# Schematic.net
KiCad netlist of a schematic drawn in EAGLE
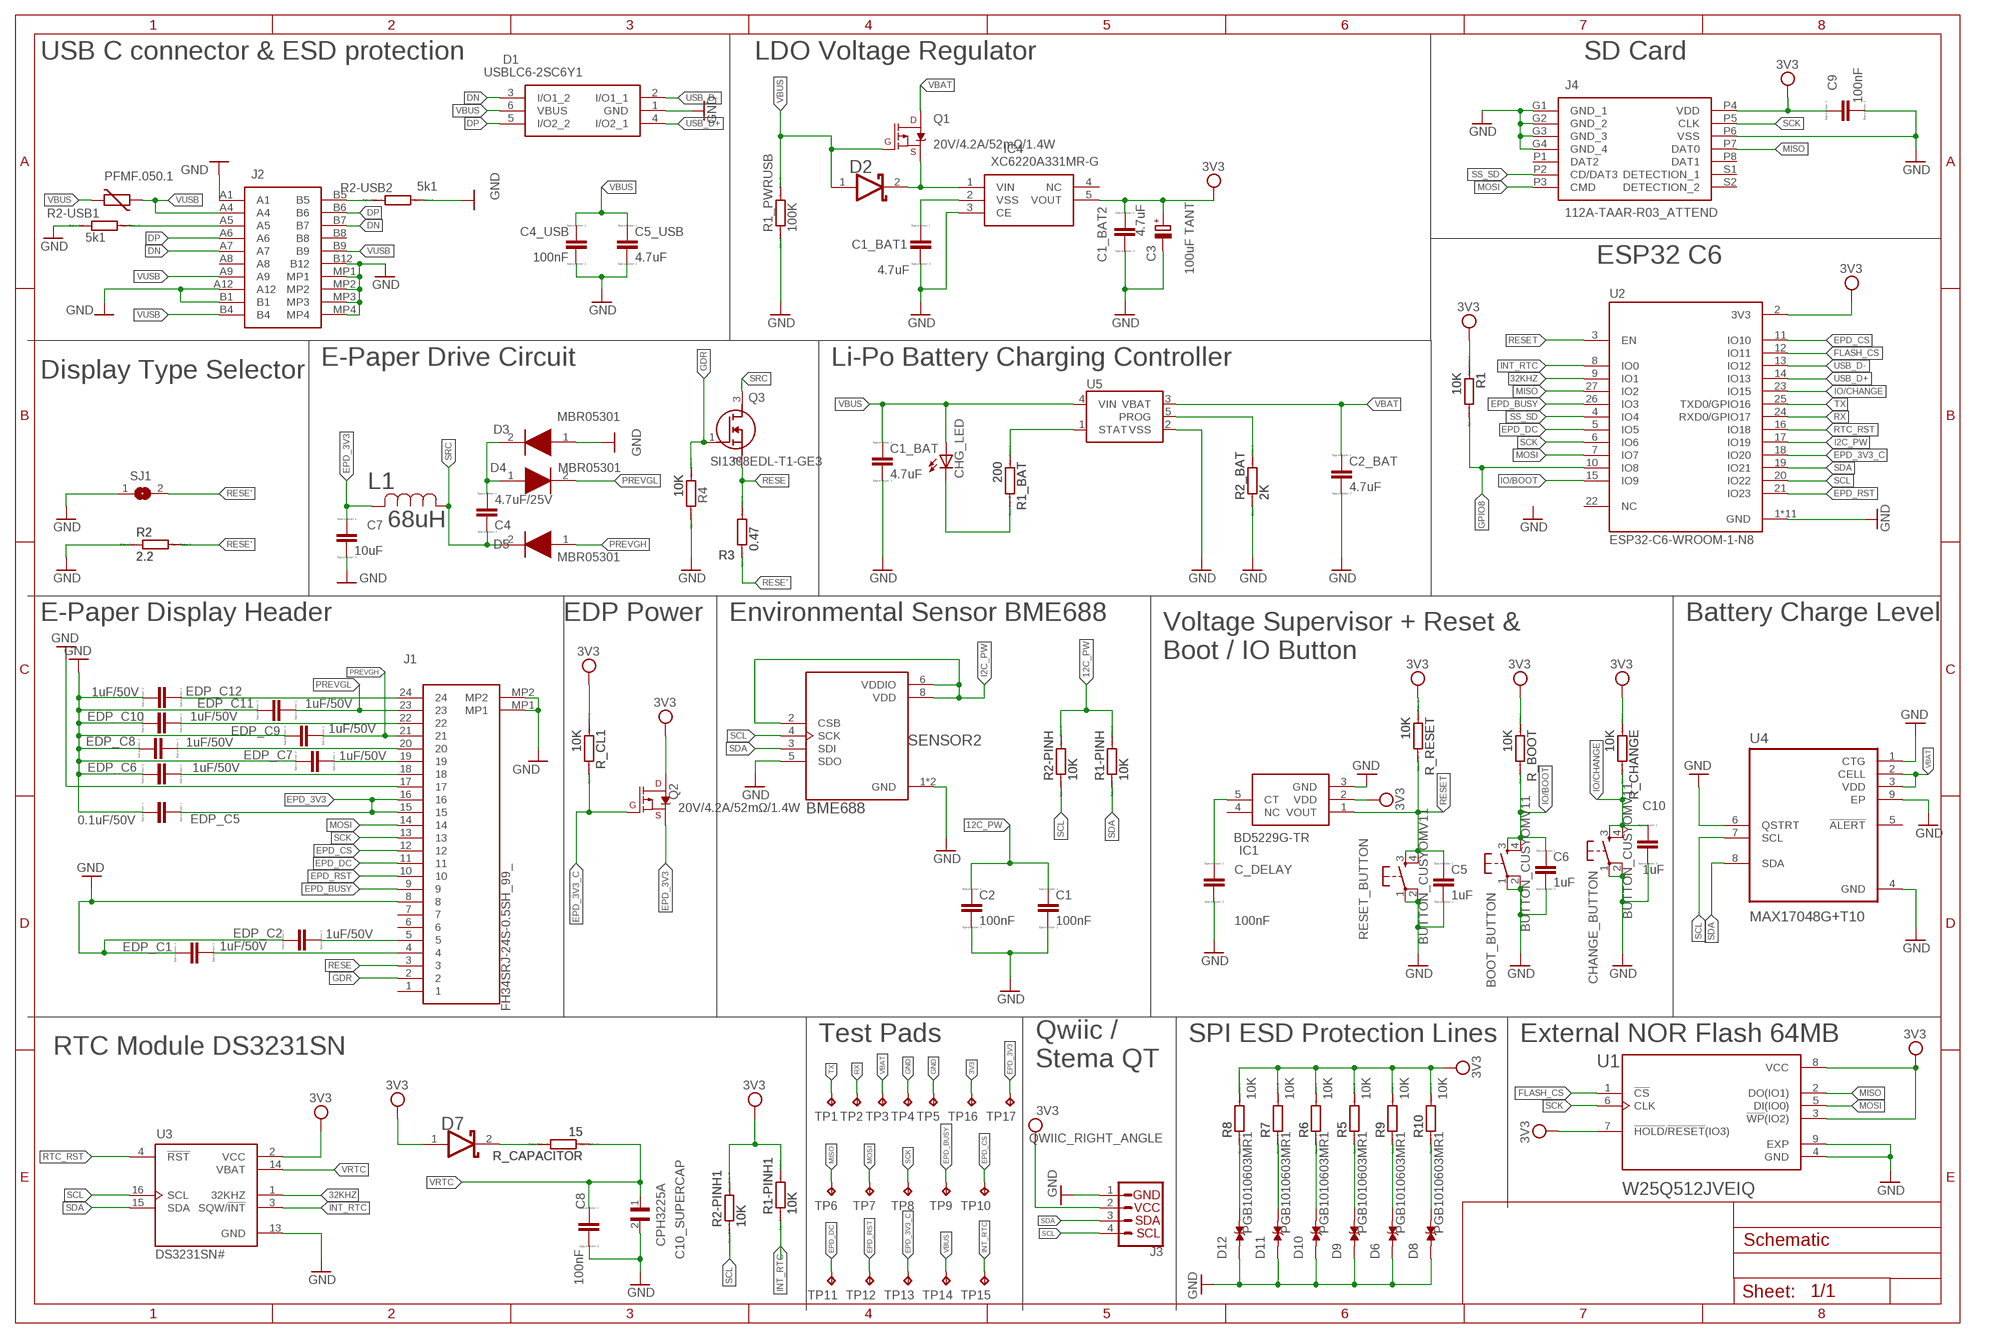
[diagram p0: schematic, sheet 1]

(export (version "E")
  (design (tool "Eeschema 10.0.6"))
  (components
    (comp (ref "BOOT_BUTTON")
      (value "BUTTON_CUSYOMV11")
      (footprint "eagle-import:MYBUTTON")
      (libsource (lib "eagle-import") (part "BUTTON_CUSYOMV11"))
    )
    (comp (ref "C1")
      (value "100nF")
      (footprint "eagle-import:ESP32_WROVER_EAGLE-LTSPICE_C0402")
      (libsource (lib "eagle-import") (part "ESP32_WROVER_EAGLE-LTSPICE_C"))
    )
    (comp (ref "C1_BAT")
      (value "4.7uF")
      (footprint "eagle-import:ESP32_WROVER_EAGLE-LTSPICE_C0402")
      (libsource (lib "eagle-import") (part "ESP32_WROVER_EAGLE-LTSPICE_C"))
    )
    (comp (ref "C1_BAT1")
      (value "4.7uF")
      (footprint "eagle-import:ESP32_WROVER_EAGLE-LTSPICE_C0402")
      (libsource (lib "eagle-import") (part "ESP32_WROVER_EAGLE-LTSPICE_C"))
    )
    (comp (ref "C1_BAT2")
      (value "4.7uF")
      (footprint "eagle-import:ESP32_WROVER_EAGLE-LTSPICE_C0402")
      (libsource (lib "eagle-import") (part "ESP32_WROVER_EAGLE-LTSPICE_C"))
    )
    (comp (ref "C2")
      (value "100nF")
      (footprint "eagle-import:ESP32_WROVER_EAGLE-LTSPICE_C0402")
      (libsource (lib "eagle-import") (part "ESP32_WROVER_EAGLE-LTSPICE_C"))
    )
    (comp (ref "C2_BAT")
      (value "4.7uF")
      (footprint "eagle-import:ESP32_WROVER_EAGLE-LTSPICE_C0402")
      (libsource (lib "eagle-import") (part "ESP32_WROVER_EAGLE-LTSPICE_C"))
    )
    (comp (ref "C3")
      (value "100uF TANT")
      (footprint "eagle-import:RCL_CT3528")
      (libsource (lib "eagle-import") (part "RCL_CPOL-EUCT3528"))
    )
    (comp (ref "C4")
      (value "4.7uF/25V")
      (footprint "eagle-import:ESP32_WROVER_EAGLE-LTSPICE_C0402")
      (libsource (lib "eagle-import") (part "ESP32_WROVER_EAGLE-LTSPICE_C"))
    )
    (comp (ref "C4_USB")
      (value "100nF")
      (footprint "eagle-import:ESP32_WROVER_EAGLE-LTSPICE_C0402")
      (libsource (lib "eagle-import") (part "ESP32_WROVER_EAGLE-LTSPICE_C"))
    )
    (comp (ref "C5")
      (value "1uF")
      (footprint "eagle-import:ESP32_WROVER_EAGLE-LTSPICE_C0402")
      (libsource (lib "eagle-import") (part "ESP32_WROVER_EAGLE-LTSPICE_C"))
    )
    (comp (ref "C5_USB")
      (value "4.7uF")
      (footprint "eagle-import:ESP32_WROVER_EAGLE-LTSPICE_C0402")
      (libsource (lib "eagle-import") (part "ESP32_WROVER_EAGLE-LTSPICE_C"))
    )
    (comp (ref "C6")
      (value "1uF")
      (footprint "eagle-import:ESP32_WROVER_EAGLE-LTSPICE_C0402")
      (libsource (lib "eagle-import") (part "ESP32_WROVER_EAGLE-LTSPICE_C"))
    )
    (comp (ref "C7")
      (value "10uF")
      (footprint "eagle-import:ESP32_WROVER_EAGLE-LTSPICE_C0402")
      (libsource (lib "eagle-import") (part "ESP32_WROVER_EAGLE-LTSPICE_C"))
    )
    (comp (ref "C8")
      (value "100nF")
      (footprint "eagle-import:ESP32_WROVER_EAGLE-LTSPICE_C0402")
      (libsource (lib "eagle-import") (part "ESP32_WROVER_EAGLE-LTSPICE_C"))
    )
    (comp (ref "C9")
      (value "100nF")
      (footprint "eagle-import:ESP32_WROVER_EAGLE-LTSPICE_C0402")
      (libsource (lib "eagle-import") (part "ESP32_WROVER_EAGLE-LTSPICE_C"))
    )
    (comp (ref "C10")
      (value "1uF")
      (footprint "eagle-import:ESP32_WROVER_EAGLE-LTSPICE_C0402")
      (libsource (lib "eagle-import") (part "ESP32_WROVER_EAGLE-LTSPICE_C"))
    )
    (comp (ref "C10_SUPERCAP")
      (value "CPH3225A")
      (footprint "eagle-import:CAPCP3225X100N")
      (fields (field (name "MF") "Seiko Instruments"))
      (libsource (lib "eagle-import") (part "CPH3225A"))
    )
    (comp (ref "CHANGE_BUTTON")
      (value "BUTTON_CUSYOMV11")
      (footprint "eagle-import:MYBUTTON")
      (libsource (lib "eagle-import") (part "BUTTON_CUSYOMV11"))
    )
    (comp (ref "CHG_LED")
      (value "1")
      (footprint "eagle-import:ADAFRUIT_CHIP-LED0603")
      (libsource (lib "eagle-import") (part "ADAFRUIT_LEDCHIP-LED0603"))
    )
    (comp (ref "C_DELAY")
      (value "100nF")
      (footprint "eagle-import:ESP32_WROVER_EAGLE-LTSPICE_C0402")
      (libsource (lib "eagle-import") (part "ESP32_WROVER_EAGLE-LTSPICE_C"))
    )
    (comp (ref "D1")
      (value "USBLC6-2SC6Y1")
      (footprint "eagle-import:SOT95P280X145-6N")
      (libsource (lib "eagle-import") (part "USBLC6-2SC6Y1"))
    )
    (comp (ref "D2")
      (value "ESP32_WROVER_AVX---SD0805S020S1R0_AVX_SD0805S020S1R0_0_0")
      (footprint "eagle-import:ESP32_WROVER_AVX---SD0805S020S1R0_AVX_SD0805S020S1R0_0")
      (libsource (lib "eagle-import") (part "ESP32_WROVER_AVX---SD0805S020S1R0_AVX_SD0805S020S1R0_0_0"))
    )
    (comp (ref "D3")
      (value "MBR05301")
      (footprint "eagle-import:SOD3716X135N")
      (libsource (lib "eagle-import") (part "MBR05301"))
    )
    (comp (ref "D4")
      (value "MBR05301")
      (footprint "eagle-import:SOD3716X135N")
      (libsource (lib "eagle-import") (part "MBR05301"))
    )
    (comp (ref "D5")
      (value "MBR05301")
      (footprint "eagle-import:SOD3716X135N")
      (libsource (lib "eagle-import") (part "MBR05301"))
    )
    (comp (ref "D6")
      (value "PGB1010603MR1")
      (footprint "eagle-import:DIOC1608X36N")
      (libsource (lib "eagle-import") (part "PGB1010603MR1"))
    )
    (comp (ref "D7")
      (value "SD805S020S1R0")
      (footprint "eagle-import:ESP32_WROVER_AVX---SD0805S020S1R0_AVX_SD0805S020S1R0_0")
      (libsource (lib "eagle-import") (part "ESP32_WROVER_AVX---SD0805S020S1R0_AVX_SD0805S020S1R0_0_0"))
    )
    (comp (ref "D8")
      (value "PGB1010603MR1")
      (footprint "eagle-import:DIOC1608X36N")
      (libsource (lib "eagle-import") (part "PGB1010603MR1"))
    )
    (comp (ref "D9")
      (value "PGB1010603MR1")
      (footprint "eagle-import:DIOC1608X36N")
      (libsource (lib "eagle-import") (part "PGB1010603MR1"))
    )
    (comp (ref "D10")
      (value "PGB1010603MR1")
      (footprint "eagle-import:DIOC1608X36N")
      (libsource (lib "eagle-import") (part "PGB1010603MR1"))
    )
    (comp (ref "D11")
      (value "PGB1010603MR1")
      (footprint "eagle-import:DIOC1608X36N")
      (libsource (lib "eagle-import") (part "PGB1010603MR1"))
    )
    (comp (ref "D12")
      (value "PGB1010603MR1")
      (footprint "eagle-import:DIOC1608X36N")
      (libsource (lib "eagle-import") (part "PGB1010603MR1"))
    )
    (comp (ref "EDP_C1")
      (value "1uF/50V")
      (footprint "eagle-import:ESP32_WROVER_EAGLE-LTSPICE_C0402")
      (libsource (lib "eagle-import") (part "ESP32_WROVER_EAGLE-LTSPICE_C"))
    )
    (comp (ref "EDP_C2")
      (value "1uF/50V")
      (footprint "eagle-import:ESP32_WROVER_EAGLE-LTSPICE_C0402")
      (libsource (lib "eagle-import") (part "ESP32_WROVER_EAGLE-LTSPICE_C"))
    )
    (comp (ref "EDP_C5")
      (value "0.1uF/50V")
      (footprint "eagle-import:ESP32_WROVER_EAGLE-LTSPICE_C0402")
      (libsource (lib "eagle-import") (part "ESP32_WROVER_EAGLE-LTSPICE_C"))
    )
    (comp (ref "EDP_C6")
      (value "1uF/50V")
      (footprint "eagle-import:ESP32_WROVER_EAGLE-LTSPICE_C0402")
      (libsource (lib "eagle-import") (part "ESP32_WROVER_EAGLE-LTSPICE_C"))
    )
    (comp (ref "EDP_C7")
      (value "1uF/50V")
      (footprint "eagle-import:ESP32_WROVER_EAGLE-LTSPICE_C0402")
      (libsource (lib "eagle-import") (part "ESP32_WROVER_EAGLE-LTSPICE_C"))
    )
    (comp (ref "EDP_C8")
      (value "1uF/50V")
      (footprint "eagle-import:ESP32_WROVER_EAGLE-LTSPICE_C0402")
      (libsource (lib "eagle-import") (part "ESP32_WROVER_EAGLE-LTSPICE_C"))
    )
    (comp (ref "EDP_C9")
      (value "1uF/50V")
      (footprint "eagle-import:ESP32_WROVER_EAGLE-LTSPICE_C0402")
      (libsource (lib "eagle-import") (part "ESP32_WROVER_EAGLE-LTSPICE_C"))
    )
    (comp (ref "EDP_C10")
      (value "1uF/50V")
      (footprint "eagle-import:ESP32_WROVER_EAGLE-LTSPICE_C0402")
      (libsource (lib "eagle-import") (part "ESP32_WROVER_EAGLE-LTSPICE_C"))
    )
    (comp (ref "EDP_C11")
      (value "1uF/50V")
      (footprint "eagle-import:ESP32_WROVER_EAGLE-LTSPICE_C0402")
      (libsource (lib "eagle-import") (part "ESP32_WROVER_EAGLE-LTSPICE_C"))
    )
    (comp (ref "EDP_C12")
      (value "1uF/50V")
      (footprint "eagle-import:ESP32_WROVER_EAGLE-LTSPICE_C0402")
      (libsource (lib "eagle-import") (part "ESP32_WROVER_EAGLE-LTSPICE_C"))
    )
    (comp (ref "IC1")
      (value "BD5229G-TR")
      (footprint "eagle-import:SOT95P280X125-5N")
      (fields (field (name "MOUSER_PART_NUMBER") "755-BD5229G-TR"))
      (libsource (lib "eagle-import") (part "BD5229G-TR"))
    )
    (comp (ref "IC4")
      (value "XC6220A331MR-G")
      (footprint "eagle-import:SOT95P280X120-5N")
      (fields (field (name "MOUSER_PART_NUMBER") "865-XC6220A331MR-G"))
      (libsource (lib "eagle-import") (part "XC6220A331MR-G"))
    )
    (comp (ref "J1")
      (value "FH34SRJ-24S-0.5SH_99_")
      (footprint "eagle-import:FH34SRJ24S05SH99")
      (fields
        (field (name "MANUFACTURER_PART_NUMBER") "FH34SRJ-24S-0.5SH(99)")
        (field (name "MOUSER_PART_NUMBER") "798-FH34SRJ24S05SH99")
      )
      (libsource (lib "eagle-import") (part "FH34SRJ-24S-0.5SH_99_"))
    )
    (comp (ref "J2")
      (value "SAMACSYS_PARTS_USB4110-GF-A")
      (footprint "eagle-import:SAMACSYS_PARTS_USB4110GFA")
      (fields
        (field (name "MANUFACTURER_PART_NUMBER") "USB4110-GF-A")
        (field (name "MOUSER_PART_NUMBER") "640-USB4110-GF-A")
      )
      (libsource (lib "eagle-import") (part "SAMACSYS_PARTS_USB4110-GF-A"))
    )
    (comp (ref "J3")
      (value "QWIIC_RIGHT_ANGLE")
      (footprint "eagle-import:JST04_1MM_RA")
      (libsource (lib "eagle-import") (part "QWIIC_CONNECTORJS-1MM"))
    )
    (comp (ref "J4")
      (value "112A-TAAR-R03_ATTEND")
      (footprint "eagle-import:112ATAARR03ATTEND")
      (fields (field (name "MANUFACTURER_PART_NUMBER") "112A-TAAR-R03 ATTEND"))
      (libsource (lib "eagle-import") (part "112A-TAAR-R03_ATTEND"))
    )
    (comp (ref "L1")
      (value "68uH")
      (footprint "eagle-import:IND_4828-WE-TPC_WRE")
      (fields
        (field (name "MANUFACTURER_PART_NUMBER") "744043680")
        (field (name "COPYRIGHT") "Copyright (C) 2024 Ultra Librarian. All rights reserved.")
      )
      (libsource (lib "eagle-import") (part "744043680IND_4828-WE-TPC_WRE"))
    )
    (comp (ref "PFMF.050.1")
      (value "ESP32C6_VARISTORCN1812")
      (footprint "eagle-import:ESP32C6_VARISTOR_CT_CN1812")
      (libsource (lib "eagle-import") (part "ESP32C6_VARISTORCN1812"))
    )
    (comp (ref "Q1")
      (value "20V/4.2A/52mΩ/1.4W")
      (footprint "eagle-import:ESP32_WROVER_SPARKFUN-DISCRETESEMI_SOT23-3")
      (libsource (lib "eagle-import") (part "ESP32_WROVER_SPARKFUN-DISCRETESEMI_MOSFET_PCH"))
    )
    (comp (ref "Q2")
      (value "20V/4.2A/52mΩ/1.4W")
      (footprint "eagle-import:ESP32_WROVER_SPARKFUN-DISCRETESEMI_SOT23-3")
      (libsource (lib "eagle-import") (part "ESP32_WROVER_SPARKFUN-DISCRETESEMI_MOSFET_PCH"))
    )
    (comp (ref "Q3")
      (value "SI1308EDL-T1-GE3")
      (footprint "eagle-import:SOT65P210X110-3N")
      (fields (field (name "MF") "Vishay Siliconix"))
      (libsource (lib "eagle-import") (part "SI1308EDL-T1-GE3"))
    )
    (comp (ref "R1")
      (value "10K")
      (footprint "eagle-import:ESP32_WROVER_EAGLE-LTSPICE_R0402")
      (libsource (lib "eagle-import") (part "ESP32_WROVER_EAGLE-LTSPICE_R"))
    )
    (comp (ref "R1-PINH")
      (value "10K")
      (footprint "eagle-import:ESP32_WROVER_EAGLE-LTSPICE_R0402")
      (libsource (lib "eagle-import") (part "ESP32_WROVER_EAGLE-LTSPICE_R"))
    )
    (comp (ref "R1-PINH1")
      (value "10K")
      (footprint "eagle-import:ESP32_WROVER_EAGLE-LTSPICE_R0402")
      (libsource (lib "eagle-import") (part "ESP32_WROVER_EAGLE-LTSPICE_R"))
    )
    (comp (ref "R1_BAT")
      (value "200")
      (footprint "eagle-import:ESP32_WROVER_EAGLE-LTSPICE_R0402")
      (libsource (lib "eagle-import") (part "ESP32_WROVER_EAGLE-LTSPICE_R"))
    )
    (comp (ref "R1_PWRUSB")
      (value "100K")
      (footprint "eagle-import:ESP32_WROVER_EAGLE-LTSPICE_R0402")
      (libsource (lib "eagle-import") (part "ESP32_WROVER_EAGLE-LTSPICE_R"))
    )
    (comp (ref "R2")
      (value "2.2")
      (footprint "eagle-import:ESP32_WROVER_EAGLE-LTSPICE_R0402")
      (libsource (lib "eagle-import") (part "ESP32_WROVER_EAGLE-LTSPICE_R"))
    )
    (comp (ref "R2-PINH")
      (value "10K")
      (footprint "eagle-import:ESP32_WROVER_EAGLE-LTSPICE_R0402")
      (libsource (lib "eagle-import") (part "ESP32_WROVER_EAGLE-LTSPICE_R"))
    )
    (comp (ref "R2-PINH1")
      (value "10K")
      (footprint "eagle-import:ESP32_WROVER_EAGLE-LTSPICE_R0402")
      (libsource (lib "eagle-import") (part "ESP32_WROVER_EAGLE-LTSPICE_R"))
    )
    (comp (ref "R2-USB1")
      (value "5k1")
      (footprint "eagle-import:ESP32_WROVER_EAGLE-LTSPICE_R0402")
      (libsource (lib "eagle-import") (part "ESP32_WROVER_EAGLE-LTSPICE_R"))
    )
    (comp (ref "R2-USB2")
      (value "5k1")
      (footprint "eagle-import:ESP32_WROVER_EAGLE-LTSPICE_R0402")
      (libsource (lib "eagle-import") (part "ESP32_WROVER_EAGLE-LTSPICE_R"))
    )
    (comp (ref "R2_BAT")
      (value "2K")
      (footprint "eagle-import:ESP32_WROVER_EAGLE-LTSPICE_R0402")
      (libsource (lib "eagle-import") (part "ESP32_WROVER_EAGLE-LTSPICE_R"))
    )
    (comp (ref "R3")
      (value "0.47")
      (footprint "eagle-import:ESP32_WROVER_EAGLE-LTSPICE_R0402")
      (libsource (lib "eagle-import") (part "ESP32_WROVER_EAGLE-LTSPICE_R"))
    )
    (comp (ref "R4")
      (value "10K")
      (footprint "eagle-import:ESP32_WROVER_EAGLE-LTSPICE_R0402")
      (libsource (lib "eagle-import") (part "ESP32_WROVER_EAGLE-LTSPICE_R"))
    )
    (comp (ref "R5")
      (value "10K")
      (footprint "eagle-import:ESP32_WROVER_EAGLE-LTSPICE_R0402")
      (libsource (lib "eagle-import") (part "ESP32_WROVER_EAGLE-LTSPICE_R"))
    )
    (comp (ref "R6")
      (value "10K")
      (footprint "eagle-import:ESP32_WROVER_EAGLE-LTSPICE_R0402")
      (libsource (lib "eagle-import") (part "ESP32_WROVER_EAGLE-LTSPICE_R"))
    )
    (comp (ref "R7")
      (value "10K")
      (footprint "eagle-import:ESP32_WROVER_EAGLE-LTSPICE_R0402")
      (libsource (lib "eagle-import") (part "ESP32_WROVER_EAGLE-LTSPICE_R"))
    )
    (comp (ref "R8")
      (value "10K")
      (footprint "eagle-import:ESP32_WROVER_EAGLE-LTSPICE_R0402")
      (libsource (lib "eagle-import") (part "ESP32_WROVER_EAGLE-LTSPICE_R"))
    )
    (comp (ref "R9")
      (value "10K")
      (footprint "eagle-import:ESP32_WROVER_EAGLE-LTSPICE_R0402")
      (libsource (lib "eagle-import") (part "ESP32_WROVER_EAGLE-LTSPICE_R"))
    )
    (comp (ref "R10")
      (value "10K")
      (footprint "eagle-import:ESP32_WROVER_EAGLE-LTSPICE_R0402")
      (libsource (lib "eagle-import") (part "ESP32_WROVER_EAGLE-LTSPICE_R"))
    )
    (comp (ref "RESET_BUTTON")
      (value "BUTTON_CUSYOMV11")
      (footprint "eagle-import:MYBUTTON")
      (libsource (lib "eagle-import") (part "BUTTON_CUSYOMV11"))
    )
    (comp (ref "R_BOOT")
      (value "10K")
      (footprint "eagle-import:ESP32_WROVER_EAGLE-LTSPICE_R0402")
      (libsource (lib "eagle-import") (part "ESP32_WROVER_EAGLE-LTSPICE_R"))
    )
    (comp (ref "R_CAPACITOR")
      (value "15")
      (footprint "eagle-import:ESP32_WROVER_EAGLE-LTSPICE_R0402")
      (libsource (lib "eagle-import") (part "ESP32_WROVER_EAGLE-LTSPICE_R"))
    )
    (comp (ref "R_CHANGE")
      (value "10K")
      (footprint "eagle-import:ESP32_WROVER_EAGLE-LTSPICE_R0402")
      (libsource (lib "eagle-import") (part "ESP32_WROVER_EAGLE-LTSPICE_R"))
    )
    (comp (ref "R_CL1")
      (value "10K")
      (footprint "eagle-import:ESP32_WROVER_EAGLE-LTSPICE_R0402")
      (libsource (lib "eagle-import") (part "ESP32_WROVER_EAGLE-LTSPICE_R"))
    )
    (comp (ref "R_RESET")
      (value "10K")
      (footprint "eagle-import:ESP32_WROVER_EAGLE-LTSPICE_R0402")
      (libsource (lib "eagle-import") (part "ESP32_WROVER_EAGLE-LTSPICE_R"))
    )
    (comp (ref "SENSOR2")
      (value "BME688")
      (footprint "eagle-import:ESP32_WROVER_BME680_PSON80P300X300X100-8N")
      (fields (field (name "MF") "Bosch Sensortec") (field (name "MP") "BME680"))
      (libsource (lib "eagle-import") (part "ESP32_WROVER_BME680_BME680"))
    )
    (comp (ref "SJ1") (value "1") (footprint "eagle-import:SJ") (libsource (lib "eagle-import") (part "SJ")))
    (comp (ref "TP1")
      (value "TP")
      (footprint "eagle-import:TP20R")
      (libsource (lib "eagle-import") (part "TP"))
    )
    (comp (ref "TP2")
      (value "TP")
      (footprint "eagle-import:TP20R")
      (libsource (lib "eagle-import") (part "TP"))
    )
    (comp (ref "TP3")
      (value "TP")
      (footprint "eagle-import:TP20R")
      (libsource (lib "eagle-import") (part "TP"))
    )
    (comp (ref "TP4")
      (value "TP")
      (footprint "eagle-import:TP20R")
      (libsource (lib "eagle-import") (part "TP"))
    )
    (comp (ref "TP5")
      (value "TP")
      (footprint "eagle-import:TP20R")
      (libsource (lib "eagle-import") (part "TP"))
    )
    (comp (ref "TP6")
      (value "TP")
      (footprint "eagle-import:TP20R")
      (libsource (lib "eagle-import") (part "TP"))
    )
    (comp (ref "TP7")
      (value "TP")
      (footprint "eagle-import:TP20R")
      (libsource (lib "eagle-import") (part "TP"))
    )
    (comp (ref "TP8")
      (value "TP")
      (footprint "eagle-import:TP20R")
      (libsource (lib "eagle-import") (part "TP"))
    )
    (comp (ref "TP9")
      (value "TP")
      (footprint "eagle-import:TP20R")
      (libsource (lib "eagle-import") (part "TP"))
    )
    (comp (ref "TP10")
      (value "TP")
      (footprint "eagle-import:TP20R")
      (libsource (lib "eagle-import") (part "TP"))
    )
    (comp (ref "TP11")
      (value "TP")
      (footprint "eagle-import:TP20R")
      (libsource (lib "eagle-import") (part "TP"))
    )
    (comp (ref "TP12")
      (value "TP")
      (footprint "eagle-import:TP20R")
      (libsource (lib "eagle-import") (part "TP"))
    )
    (comp (ref "TP13")
      (value "TP")
      (footprint "eagle-import:TP20R")
      (libsource (lib "eagle-import") (part "TP"))
    )
    (comp (ref "TP14")
      (value "TP")
      (footprint "eagle-import:TP20R")
      (libsource (lib "eagle-import") (part "TP"))
    )
    (comp (ref "TP15")
      (value "TP")
      (footprint "eagle-import:TP20R")
      (libsource (lib "eagle-import") (part "TP"))
    )
    (comp (ref "TP16")
      (value "TP")
      (footprint "eagle-import:TP20R")
      (libsource (lib "eagle-import") (part "TP"))
    )
    (comp (ref "TP17")
      (value "TP")
      (footprint "eagle-import:TP20R")
      (libsource (lib "eagle-import") (part "TP"))
    )
    (comp (ref "U1")
      (value "W25Q512JVEIQ")
      (footprint "eagle-import:SON127P600X800X80-9N")
      (fields (field (name "MF") "Winbond Electronics"))
      (libsource (lib "eagle-import") (part "W25Q512JVEIQ"))
    )
    (comp (ref "U2")
      (value "ESP32-C6-WROOM-1-N8")
      (footprint "eagle-import:XCVR_ESP32-C6-WROOM-1-N8")
      (fields (field (name "MF") "Espressif Systems"))
      (libsource (lib "eagle-import") (part "ESP32-C6-WROOM-1-N8"))
    )
    (comp (ref "U3")
      (value "DS3231SN#")
      (footprint "eagle-import:SOIC127P1032X265-16N")
      (fields (field (name "MF") "Analog Devices"))
      (libsource (lib "eagle-import") (part "DS3231SN#"))
    )
    (comp (ref "U4")
      (value "MAX17048G+T10")
      (footprint "eagle-import:SON50P200X200X80-9N")
      (fields (field (name "MF") "Analog Devices"))
      (libsource (lib "eagle-import") (part "MAX17048G+T10"))
    )
    (comp (ref "U5")
      (value "MCP73831")
      (footprint "eagle-import:ESP32_WROVER_SPARKFUN-IC-POWER_SOT23-5")
      (libsource (lib "eagle-import") (part "ESP32_WROVER_SPARKFUN-IC-POWER_MCP73831"))
    )
  )
  (nets
    (net (code "1") (name "3V3") (class "Default")
      (node (ref "C1_BAT2") (pin "1") (pinfunction "1_1") (pintype "passive"))
      (node (ref "C3") (pin "+") (pinfunction "+_+") (pintype "passive"))
      (node (ref "C9") (pin "1") (pinfunction "1_1") (pintype "passive"))
      (node (ref "D7") (pin "1") (pinfunction "ANODE_1") (pintype "bidirectional"))
      (node (ref "IC1") (pin "2") (pinfunction "VDD_2") (pintype "bidirectional"))
      (node (ref "IC4") (pin "5") (pinfunction "VOUT_5") (pintype "bidirectional"))
      (node (ref "J3") (pin "2") (pinfunction "2_2") (pintype "power_in"))
      (node (ref "J4") (pin "P4") (pinfunction "VDD_P4") (pintype "bidirectional"))
      (node (ref "Q2") (pin "1") (pinfunction "D_1") (pintype "bidirectional"))
      (node (ref "R1") (pin "1") (pinfunction "1_1") (pintype "passive"))
      (node (ref "R1-PINH1") (pin "2") (pinfunction "2_2") (pintype "passive"))
      (node (ref "R10") (pin "2") (pinfunction "2_2") (pintype "passive"))
      (node (ref "R2-PINH1") (pin "2") (pinfunction "2_2") (pintype "passive"))
      (node (ref "R5") (pin "2") (pinfunction "2_2") (pintype "passive"))
      (node (ref "R6") (pin "2") (pinfunction "2_2") (pintype "passive"))
      (node (ref "R7") (pin "2") (pinfunction "2_2") (pintype "passive"))
      (node (ref "R8") (pin "2") (pinfunction "2_2") (pintype "passive"))
      (node (ref "R9") (pin "2") (pinfunction "2_2") (pintype "passive"))
      (node (ref "R_BOOT") (pin "1") (pinfunction "1_1") (pintype "passive"))
      (node (ref "R_CHANGE") (pin "1") (pinfunction "1_1") (pintype "passive"))
      (node (ref "R_CL1") (pin "1") (pinfunction "1_1") (pintype "passive"))
      (node (ref "R_RESET") (pin "1") (pinfunction "1_1") (pintype "passive"))
      (node (ref "TP16") (pin "TP") (pinfunction "TP_TP") (pintype "input"))
      (node (ref "U1") (pin "3") (pinfunction "~{WP}(IO2)_3") (pintype "bidirectional"))
      (node (ref "U1") (pin "7") (pinfunction "~{HOLD}/~{RESET}(IO3)_7") (pintype "bidirectional"))
      (node (ref "U1") (pin "8") (pinfunction "VCC_8") (pintype "power_in"))
      (node (ref "U2") (pin "2") (pinfunction "3V3_2") (pintype "power_in"))
      (node (ref "U3") (pin "2") (pinfunction "VCC_2") (pintype "power_in"))
    )
    (net (code "2") (name "12C_PW") (class "Default")
      (node (ref "C1") (pin "1") (pinfunction "1_1") (pintype "passive"))
      (node (ref "C2") (pin "1") (pinfunction "1_1") (pintype "passive"))
      (node (ref "R1-PINH") (pin "2") (pinfunction "2_2") (pintype "passive"))
      (node (ref "R2-PINH") (pin "2") (pinfunction "2_2") (pintype "passive"))
    )
    (net (code "3") (name "32KHZ") (class "Default")
      (node (ref "U2") (pin "9") (pinfunction "IO1_9") (pintype "bidirectional"))
      (node (ref "U3") (pin "1") (pinfunction "32KHZ_1") (pintype "output"))
    )
    (net (code "4") (name "DN") (class "Default")
      (node (ref "D1") (pin "3") (pinfunction "I/O1_2_3") (pintype "bidirectional"))
      (node (ref "J2") (pin "A7") (pinfunction "A7_A7") (pintype "bidirectional"))
      (node (ref "J2") (pin "B7") (pinfunction "B7_B7") (pintype "bidirectional"))
    )
    (net (code "5") (name "DP") (class "Default")
      (node (ref "D1") (pin "5") (pinfunction "I/O2_2_5") (pintype "bidirectional"))
      (node (ref "J2") (pin "A6") (pinfunction "A6_A6") (pintype "bidirectional"))
      (node (ref "J2") (pin "B6") (pinfunction "B6_B6") (pintype "bidirectional"))
    )
    (net (code "6") (name "EPD_3V3") (class "Default")
      (node (ref "C7") (pin "1") (pinfunction "1_1") (pintype "passive"))
      (node (ref "EDP_C5") (pin "1") (pinfunction "1_1") (pintype "passive"))
      (node (ref "J1") (pin "15") (pinfunction "15_15") (pintype "bidirectional"))
      (node (ref "J1") (pin "16") (pinfunction "16_16") (pintype "bidirectional"))
      (node (ref "L1") (pin "2") (pinfunction "2_2") (pintype "passive"))
      (node (ref "Q2") (pin "3") (pinfunction "S_3") (pintype "bidirectional"))
      (node (ref "TP17") (pin "TP") (pinfunction "TP_TP") (pintype "input"))
    )
    (net (code "7") (name "EPD_3V3_C") (class "Default")
      (node (ref "Q2") (pin "2") (pinfunction "G_2") (pintype "bidirectional"))
      (node (ref "R_CL1") (pin "2") (pinfunction "2_2") (pintype "passive"))
      (node (ref "TP13") (pin "TP") (pinfunction "TP_TP") (pintype "input"))
      (node (ref "U2") (pin "18") (pinfunction "IO20_18") (pintype "bidirectional"))
    )
    (net (code "8") (name "EPD_BUSY") (class "Default")
      (node (ref "J1") (pin "9") (pinfunction "9_9") (pintype "bidirectional"))
      (node (ref "TP9") (pin "TP") (pinfunction "TP_TP") (pintype "input"))
      (node (ref "U2") (pin "26") (pinfunction "IO3_26") (pintype "bidirectional"))
    )
    (net (code "9") (name "EPD_CS") (class "Default")
      (node (ref "J1") (pin "12") (pinfunction "12_12") (pintype "bidirectional"))
      (node (ref "TP10") (pin "TP") (pinfunction "TP_TP") (pintype "input"))
      (node (ref "U2") (pin "11") (pinfunction "IO10_11") (pintype "bidirectional"))
    )
    (net (code "10") (name "EPD_DC") (class "Default")
      (node (ref "J1") (pin "11") (pinfunction "11_11") (pintype "bidirectional"))
      (node (ref "TP11") (pin "TP") (pinfunction "TP_TP") (pintype "input"))
      (node (ref "U2") (pin "5") (pinfunction "IO5_5") (pintype "bidirectional"))
    )
    (net (code "11") (name "EPD_RST") (class "Default")
      (node (ref "J1") (pin "10") (pinfunction "10_10") (pintype "bidirectional"))
      (node (ref "TP12") (pin "TP") (pinfunction "TP_TP") (pintype "input"))
      (node (ref "U2") (pin "21") (pinfunction "IO23_21") (pintype "bidirectional"))
    )
    (net (code "12") (name "FLASH_CS") (class "Default")
      (node (ref "U1") (pin "1") (pinfunction "~{CS}_1") (pintype "input"))
      (node (ref "U2") (pin "12") (pinfunction "IO11_12") (pintype "bidirectional"))
    )
    (net (code "13") (name "GDR") (class "Default")
      (node (ref "J1") (pin "2") (pinfunction "2_2") (pintype "bidirectional"))
      (node (ref "Q3") (pin "1") (pinfunction "G_1") (pintype "bidirectional"))
      (node (ref "R4") (pin "1") (pinfunction "1_1") (pintype "passive"))
    )
    (net (code "14") (name "GND") (class "Default")
      (node (ref "BOOT_BUTTON") (pin "1") (pinfunction "1_1") (pintype "passive"))
      (node (ref "BOOT_BUTTON") (pin "2") (pinfunction "2_2") (pintype "passive"))
      (node (ref "C1") (pin "2") (pinfunction "2_2") (pintype "passive"))
      (node (ref "C10") (pin "2") (pinfunction "2_2") (pintype "passive"))
      (node (ref "C10_SUPERCAP") (pin "2") (pinfunction "2_2") (pintype "passive"))
      (node (ref "C1_BAT") (pin "2") (pinfunction "2_2") (pintype "passive"))
      (node (ref "C1_BAT1") (pin "2") (pinfunction "2_2") (pintype "passive"))
      (node (ref "C1_BAT2") (pin "2") (pinfunction "2_2") (pintype "passive"))
      (node (ref "C2") (pin "2") (pinfunction "2_2") (pintype "passive"))
      (node (ref "C2_BAT") (pin "2") (pinfunction "2_2") (pintype "passive"))
      (node (ref "C3") (pin "-") (pinfunction "-_-") (pintype "passive"))
      (node (ref "C4_USB") (pin "2") (pinfunction "2_2") (pintype "passive"))
      (node (ref "C5") (pin "2") (pinfunction "2_2") (pintype "passive"))
      (node (ref "C5_USB") (pin "2") (pinfunction "2_2") (pintype "passive"))
      (node (ref "C6") (pin "2") (pinfunction "2_2") (pintype "passive"))
      (node (ref "C7") (pin "2") (pinfunction "2_2") (pintype "passive"))
      (node (ref "C8") (pin "2") (pinfunction "2_2") (pintype "passive"))
      (node (ref "C9") (pin "2") (pinfunction "2_2") (pintype "passive"))
      (node (ref "CHANGE_BUTTON") (pin "1") (pinfunction "1_1") (pintype "passive"))
      (node (ref "CHANGE_BUTTON") (pin "2") (pinfunction "2_2") (pintype "passive"))
      (node (ref "C_DELAY") (pin "2") (pinfunction "2_2") (pintype "passive"))
      (node (ref "D1") (pin "1") (pinfunction "GND_1") (pintype "bidirectional"))
      (node (ref "D10") (pin "1") (pinfunction "1_1") (pintype "passive"))
      (node (ref "D11") (pin "1") (pinfunction "1_1") (pintype "passive"))
      (node (ref "D12") (pin "1") (pinfunction "1_1") (pintype "passive"))
      (node (ref "D3") (pin "1") (pinfunction "A_1") (pintype "bidirectional"))
      (node (ref "D6") (pin "1") (pinfunction "1_1") (pintype "passive"))
      (node (ref "D8") (pin "1") (pinfunction "1_1") (pintype "passive"))
      (node (ref "D9") (pin "1") (pinfunction "1_1") (pintype "passive"))
      (node (ref "EDP_C1") (pin "2") (pinfunction "2_2") (pintype "passive"))
      (node (ref "EDP_C10") (pin "2") (pinfunction "2_2") (pintype "passive"))
      (node (ref "EDP_C11") (pin "2") (pinfunction "2_2") (pintype "passive"))
      (node (ref "EDP_C12") (pin "2") (pinfunction "2_2") (pintype "passive"))
      (node (ref "EDP_C2") (pin "2") (pinfunction "2_2") (pintype "passive"))
      (node (ref "EDP_C5") (pin "2") (pinfunction "2_2") (pintype "passive"))
      (node (ref "EDP_C6") (pin "2") (pinfunction "2_2") (pintype "passive"))
      (node (ref "EDP_C7") (pin "2") (pinfunction "2_2") (pintype "passive"))
      (node (ref "EDP_C8") (pin "2") (pinfunction "2_2") (pintype "passive"))
      (node (ref "EDP_C9") (pin "2") (pinfunction "2_2") (pintype "passive"))
      (node (ref "IC1") (pin "3") (pinfunction "GND_3") (pintype "bidirectional"))
      (node (ref "IC4") (pin "3") (pinfunction "CE_3") (pintype "bidirectional"))
      (node (ref "J1") (pin "17") (pinfunction "17_17") (pintype "bidirectional"))
      (node (ref "J1") (pin "8") (pinfunction "8_8") (pintype "bidirectional"))
      (node (ref "J1") (pin "MP1") (pinfunction "MP1_MP1") (pintype "bidirectional"))
      (node (ref "J1") (pin "MP2") (pinfunction "MP2_MP2") (pintype "bidirectional"))
      (node (ref "J2") (pin "A1") (pinfunction "A1_A1") (pintype "bidirectional"))
      (node (ref "J2") (pin "A12") (pinfunction "A12_A12") (pintype "bidirectional"))
      (node (ref "J2") (pin "B1") (pinfunction "B1_B1") (pintype "bidirectional"))
      (node (ref "J2") (pin "B12") (pinfunction "B12_B12") (pintype "bidirectional"))
      (node (ref "J2") (pin "MP1") (pinfunction "MP1_MP1") (pintype "bidirectional"))
      (node (ref "J2") (pin "MP2") (pinfunction "MP2_MP2") (pintype "bidirectional"))
      (node (ref "J2") (pin "MP3") (pinfunction "MP3_MP3") (pintype "bidirectional"))
      (node (ref "J2") (pin "MP4") (pinfunction "MP4_MP4") (pintype "bidirectional"))
      (node (ref "J3") (pin "1") (pinfunction "1_1") (pintype "power_in"))
      (node (ref "J4") (pin "G1") (pinfunction "GND_1_G1") (pintype "bidirectional"))
      (node (ref "J4") (pin "G2") (pinfunction "GND_2_G2") (pintype "bidirectional"))
      (node (ref "J4") (pin "G3") (pinfunction "GND_3_G3") (pintype "bidirectional"))
      (node (ref "J4") (pin "G4") (pinfunction "GND_4_G4") (pintype "bidirectional"))
      (node (ref "J4") (pin "P6") (pinfunction "VSS_P6") (pintype "bidirectional"))
      (node (ref "R1_PWRUSB") (pin "1") (pinfunction "1_1") (pintype "passive"))
      (node (ref "R2") (pin "1") (pinfunction "1_1") (pintype "passive"))
      (node (ref "R2-USB1") (pin "1") (pinfunction "1_1") (pintype "passive"))
      (node (ref "R2-USB2") (pin "2") (pinfunction "2_2") (pintype "passive"))
      (node (ref "R2_BAT") (pin "1") (pinfunction "1_1") (pintype "passive"))
      (node (ref "R4") (pin "2") (pinfunction "2_2") (pintype "passive"))
      (node (ref "RESET_BUTTON") (pin "1") (pinfunction "1_1") (pintype "passive"))
      (node (ref "RESET_BUTTON") (pin "2") (pinfunction "2_2") (pintype "passive"))
      (node (ref "SENSOR2") (pin "1") (pinfunction "GND_1") (pintype "power_in"))
      (node (ref "SENSOR2") (pin "5") (pinfunction "SDO_5") (pintype "bidirectional"))
      (node (ref "SENSOR2") (pin "7") (pinfunction "GND_7") (pintype "power_in"))
      (node (ref "SJ1") (pin "1") (pinfunction "1_1") (pintype "passive"))
      (node (ref "TP4") (pin "TP") (pinfunction "TP_TP") (pintype "input"))
      (node (ref "TP5") (pin "TP") (pinfunction "TP_TP") (pintype "input"))
      (node (ref "U1") (pin "4") (pinfunction "GND_4") (pintype "power_in"))
      (node (ref "U1") (pin "9") (pinfunction "EXP_9") (pintype "passive"))
      (node (ref "U2") (pin "1") (pinfunction "GND_1") (pintype "power_in"))
      (node (ref "U2") (pin "28") (pinfunction "GND_28") (pintype "power_in"))
      (node (ref "U2") (pin "29_1") (pinfunction "GND_29_1") (pintype "power_in"))
      (node (ref "U2") (pin "29_2") (pinfunction "GND_29_2") (pintype "power_in"))
      (node (ref "U2") (pin "29_3") (pinfunction "GND_29_3") (pintype "power_in"))
      (node (ref "U2") (pin "29_4") (pinfunction "GND_29_4") (pintype "power_in"))
      (node (ref "U2") (pin "29_5") (pinfunction "GND_29_5") (pintype "power_in"))
      (node (ref "U2") (pin "29_6") (pinfunction "GND_29_6") (pintype "power_in"))
      (node (ref "U2") (pin "29_7") (pinfunction "GND_29_7") (pintype "power_in"))
      (node (ref "U2") (pin "29_8") (pinfunction "GND_29_8") (pintype "power_in"))
      (node (ref "U2") (pin "29_9") (pinfunction "GND_29_9") (pintype "power_in"))
      (node (ref "U3") (pin "13") (pinfunction "GND_13") (pintype "power_in"))
      (node (ref "U4") (pin "1") (pinfunction "CTG_1") (pintype "power_in"))
      (node (ref "U4") (pin "4") (pinfunction "GND_4") (pintype "power_in"))
      (node (ref "U4") (pin "6") (pinfunction "QSTRT_6") (pintype "input"))
      (node (ref "U4") (pin "9") (pinfunction "EP_9") (pintype "power_in"))
      (node (ref "U5") (pin "2") (pinfunction "VSS_2") (pintype "power_in"))
    )
    (net (code "15") (name "GPIO8") (class "Default")
      (node (ref "R1") (pin "2") (pinfunction "2_2") (pintype "passive"))
      (node (ref "U2") (pin "10") (pinfunction "IO8_10") (pintype "bidirectional"))
    )
    (net (code "16") (name "I2C_PW") (class "Default")
      (node (ref "SENSOR2") (pin "2") (pinfunction "CSB_2") (pintype "input"))
      (node (ref "SENSOR2") (pin "6") (pinfunction "VDDIO_6") (pintype "power_in"))
      (node (ref "SENSOR2") (pin "8") (pinfunction "VDD_8") (pintype "power_in"))
      (node (ref "U2") (pin "17") (pinfunction "IO19_17") (pintype "bidirectional"))
    )
    (net (code "17") (name "INT_RTC") (class "Default")
      (node (ref "R1-PINH1") (pin "1") (pinfunction "1_1") (pintype "passive"))
      (node (ref "TP15") (pin "TP") (pinfunction "TP_TP") (pintype "input"))
      (node (ref "U2") (pin "8") (pinfunction "IO0_8") (pintype "bidirectional"))
      (node (ref "U3") (pin "3") (pinfunction "SQW/~{INT}_3") (pintype "output"))
    )
    (net (code "18") (name "IO{slash}BOOT") (class "Default")
      (node (ref "BOOT_BUTTON") (pin "3") (pinfunction "3_3") (pintype "passive"))
      (node (ref "BOOT_BUTTON") (pin "4") (pinfunction "4_4") (pintype "passive"))
      (node (ref "C6") (pin "1") (pinfunction "1_1") (pintype "passive"))
      (node (ref "R_BOOT") (pin "2") (pinfunction "2_2") (pintype "passive"))
      (node (ref "U2") (pin "15") (pinfunction "IO9_15") (pintype "bidirectional"))
    )
    (net (code "19") (name "IO{slash}CHANGE") (class "Default")
      (node (ref "C10") (pin "1") (pinfunction "1_1") (pintype "passive"))
      (node (ref "CHANGE_BUTTON") (pin "3") (pinfunction "3_3") (pintype "passive"))
      (node (ref "CHANGE_BUTTON") (pin "4") (pinfunction "4_4") (pintype "passive"))
      (node (ref "R_CHANGE") (pin "2") (pinfunction "2_2") (pintype "passive"))
      (node (ref "U2") (pin "23") (pinfunction "IO15_23") (pintype "bidirectional"))
    )
    (net (code "20") (name "MISO") (class "Default")
      (node (ref "J4") (pin "P7") (pinfunction "DAT0_P7") (pintype "bidirectional"))
      (node (ref "TP6") (pin "TP") (pinfunction "TP_TP") (pintype "input"))
      (node (ref "U1") (pin "2") (pinfunction "DO(IO1)_2") (pintype "bidirectional"))
      (node (ref "U2") (pin "27") (pinfunction "IO2_27") (pintype "bidirectional"))
    )
    (net (code "21") (name "MOSI") (class "Default")
      (node (ref "J1") (pin "14") (pinfunction "14_14") (pintype "bidirectional"))
      (node (ref "J4") (pin "P3") (pinfunction "CMD_P3") (pintype "bidirectional"))
      (node (ref "TP7") (pin "TP") (pinfunction "TP_TP") (pintype "input"))
      (node (ref "U1") (pin "5") (pinfunction "DI(IO0)_5") (pintype "bidirectional"))
      (node (ref "U2") (pin "7") (pinfunction "IO7_7") (pintype "bidirectional"))
    )
    (net (code "22") (name "Net-(CHG_LED-PadC)") (class "Default")
      (node (ref "CHG_LED") (pin "C") (pinfunction "C_C") (pintype "passive"))
      (node (ref "R1_BAT") (pin "2") (pinfunction "2_2") (pintype "passive"))
    )
    (net (code "23") (name "Net-(D2-CATHODE)") (class "Default")
      (node (ref "D2") (pin "2") (pinfunction "CATHODE_2") (pintype "bidirectional"))
      (node (ref "IC4") (pin "1") (pinfunction "VIN_1") (pintype "bidirectional"))
      (node (ref "Q1") (pin "3") (pinfunction "S_3") (pintype "bidirectional"))
    )
    (net (code "24") (name "Net-(D3-K)") (class "Default")
      (node (ref "C4") (pin "1") (pinfunction "1_1") (pintype "passive"))
      (node (ref "D3") (pin "2") (pinfunction "K_2") (pintype "bidirectional"))
      (node (ref "D4") (pin "1") (pinfunction "A_1") (pintype "bidirectional"))
    )
    (net (code "25") (name "Net-(D6-Pad2)") (class "Default")
      (node (ref "D6") (pin "2") (pinfunction "2_2") (pintype "passive"))
      (node (ref "R9") (pin "1") (pinfunction "1_1") (pintype "passive"))
    )
    (net (code "26") (name "Net-(D7-CATHODE)") (class "Default")
      (node (ref "D7") (pin "2") (pinfunction "CATHODE_2") (pintype "bidirectional"))
      (node (ref "R_CAPACITOR") (pin "2") (pinfunction "2_2") (pintype "passive"))
    )
    (net (code "27") (name "Net-(D8-Pad2)") (class "Default")
      (node (ref "D8") (pin "2") (pinfunction "2_2") (pintype "passive"))
      (node (ref "R10") (pin "1") (pinfunction "1_1") (pintype "passive"))
    )
    (net (code "28") (name "Net-(D9-Pad2)") (class "Default")
      (node (ref "D9") (pin "2") (pinfunction "2_2") (pintype "passive"))
      (node (ref "R5") (pin "1") (pinfunction "1_1") (pintype "passive"))
    )
    (net (code "29") (name "Net-(D10-Pad2)") (class "Default")
      (node (ref "D10") (pin "2") (pinfunction "2_2") (pintype "passive"))
      (node (ref "R6") (pin "1") (pinfunction "1_1") (pintype "passive"))
    )
    (net (code "30") (name "Net-(D11-Pad2)") (class "Default")
      (node (ref "D11") (pin "2") (pinfunction "2_2") (pintype "passive"))
      (node (ref "R7") (pin "1") (pinfunction "1_1") (pintype "passive"))
    )
    (net (code "31") (name "Net-(D12-Pad2)") (class "Default")
      (node (ref "D12") (pin "2") (pinfunction "2_2") (pintype "passive"))
      (node (ref "R8") (pin "1") (pinfunction "1_1") (pintype "passive"))
    )
    (net (code "32") (name "Net-(EDP_C1-Pad1)") (class "Default")
      (node (ref "EDP_C1") (pin "1") (pinfunction "1_1") (pintype "passive"))
      (node (ref "J1") (pin "4") (pinfunction "4_4") (pintype "bidirectional"))
    )
    (net (code "33") (name "Net-(EDP_C2-Pad1)") (class "Default")
      (node (ref "EDP_C2") (pin "1") (pinfunction "1_1") (pintype "passive"))
      (node (ref "J1") (pin "5") (pinfunction "5_5") (pintype "bidirectional"))
    )
    (net (code "34") (name "Net-(EDP_C6-Pad1)") (class "Default")
      (node (ref "EDP_C6") (pin "1") (pinfunction "1_1") (pintype "passive"))
      (node (ref "J1") (pin "18") (pinfunction "18_18") (pintype "bidirectional"))
    )
    (net (code "35") (name "Net-(EDP_C7-Pad1)") (class "Default")
      (node (ref "EDP_C7") (pin "1") (pinfunction "1_1") (pintype "passive"))
      (node (ref "J1") (pin "19") (pinfunction "19_19") (pintype "bidirectional"))
    )
    (net (code "36") (name "Net-(EDP_C8-Pad1)") (class "Default")
      (node (ref "EDP_C8") (pin "1") (pinfunction "1_1") (pintype "passive"))
      (node (ref "J1") (pin "20") (pinfunction "20_20") (pintype "bidirectional"))
    )
    (net (code "37") (name "Net-(EDP_C10-Pad1)") (class "Default")
      (node (ref "EDP_C10") (pin "1") (pinfunction "1_1") (pintype "passive"))
      (node (ref "J1") (pin "22") (pinfunction "22_22") (pintype "bidirectional"))
    )
    (net (code "38") (name "Net-(EDP_C12-Pad1)") (class "Default")
      (node (ref "EDP_C12") (pin "1") (pinfunction "1_1") (pintype "passive"))
      (node (ref "J1") (pin "24") (pinfunction "24_24") (pintype "bidirectional"))
    )
    (net (code "39") (name "Net-(IC1-CT)") (class "Default")
      (node (ref "C_DELAY") (pin "1") (pinfunction "1_1") (pintype "passive"))
      (node (ref "IC1") (pin "5") (pinfunction "CT_5") (pintype "bidirectional"))
    )
    (net (code "40") (name "Net-(IC4-VSS)") (class "Default")
      (node (ref "C1_BAT1") (pin "1") (pinfunction "1_1") (pintype "passive"))
      (node (ref "IC4") (pin "2") (pinfunction "VSS_2") (pintype "bidirectional"))
    )
    (net (code "41") (name "Net-(J2-PadA5)") (class "Default")
      (node (ref "J2") (pin "A5") (pinfunction "A5_A5") (pintype "bidirectional"))
      (node (ref "R2-USB1") (pin "2") (pinfunction "2_2") (pintype "passive"))
    )
    (net (code "42") (name "Net-(J2-PadB5)") (class "Default")
      (node (ref "J2") (pin "B5") (pinfunction "B5_B5") (pintype "bidirectional"))
      (node (ref "R2-USB2") (pin "1") (pinfunction "1_1") (pintype "passive"))
    )
    (net (code "43") (name "Net-(U5-PROG)") (class "Default")
      (node (ref "R2_BAT") (pin "2") (pinfunction "2_2") (pintype "passive"))
      (node (ref "U5") (pin "5") (pinfunction "PROG_5") (pintype "input"))
    )
    (net (code "44") (name "Net-(U5-STAT)") (class "Default")
      (node (ref "R1_BAT") (pin "1") (pinfunction "1_1") (pintype "passive"))
      (node (ref "U5") (pin "1") (pinfunction "STAT_1") (pintype "output"))
    )
    (net (code "45") (name "PREVGH") (class "Default")
      (node (ref "D5") (pin "1") (pinfunction "A_1") (pintype "bidirectional"))
      (node (ref "EDP_C9") (pin "1") (pinfunction "1_1") (pintype "passive"))
      (node (ref "J1") (pin "21") (pinfunction "21_21") (pintype "bidirectional"))
    )
    (net (code "46") (name "PREVGL") (class "Default")
      (node (ref "D4") (pin "2") (pinfunction "K_2") (pintype "bidirectional"))
      (node (ref "EDP_C11") (pin "1") (pinfunction "1_1") (pintype "passive"))
      (node (ref "J1") (pin "23") (pinfunction "23_23") (pintype "bidirectional"))
    )
    (net (code "47") (name "RESE") (class "Default")
      (node (ref "J1") (pin "3") (pinfunction "3_3") (pintype "bidirectional"))
      (node (ref "Q3") (pin "2") (pinfunction "S_2") (pintype "bidirectional"))
      (node (ref "R3") (pin "2") (pinfunction "2_2") (pintype "passive"))
    )
    (net (code "48") (name "RESE'") (class "Default")
      (node (ref "R2") (pin "2") (pinfunction "2_2") (pintype "passive"))
      (node (ref "R3") (pin "1") (pinfunction "1_1") (pintype "passive"))
      (node (ref "SJ1") (pin "2") (pinfunction "2_2") (pintype "passive"))
    )
    (net (code "49") (name "RESET") (class "Default")
      (node (ref "C5") (pin "1") (pinfunction "1_1") (pintype "passive"))
      (node (ref "IC1") (pin "1") (pinfunction "VOUT_1") (pintype "bidirectional"))
      (node (ref "RESET_BUTTON") (pin "3") (pinfunction "3_3") (pintype "passive"))
      (node (ref "RESET_BUTTON") (pin "4") (pinfunction "4_4") (pintype "passive"))
      (node (ref "R_RESET") (pin "2") (pinfunction "2_2") (pintype "passive"))
      (node (ref "U2") (pin "3") (pinfunction "EN_3") (pintype "input"))
    )
    (net (code "50") (name "RTC_RST") (class "Default")
      (node (ref "U2") (pin "16") (pinfunction "IO18_16") (pintype "bidirectional"))
      (node (ref "U3") (pin "4") (pinfunction "~{RST}_4") (pintype "input"))
    )
    (net (code "51") (name "RX") (class "Default")
      (node (ref "TP2") (pin "TP") (pinfunction "TP_TP") (pintype "input"))
      (node (ref "U2") (pin "24") (pinfunction "RXD0/GPIO17_24") (pintype "bidirectional"))
    )
    (net (code "52") (name "SCK") (class "Default")
      (node (ref "J1") (pin "13") (pinfunction "13_13") (pintype "bidirectional"))
      (node (ref "J4") (pin "P5") (pinfunction "CLK_P5") (pintype "bidirectional"))
      (node (ref "TP8") (pin "TP") (pinfunction "TP_TP") (pintype "input"))
      (node (ref "U1") (pin "6") (pinfunction "CLK_6") (pintype "input"))
      (node (ref "U2") (pin "6") (pinfunction "IO6_6") (pintype "bidirectional"))
    )
    (net (code "53") (name "SCL") (class "Default")
      (node (ref "J3") (pin "4") (pinfunction "4_4") (pintype "passive"))
      (node (ref "R2-PINH") (pin "1") (pinfunction "1_1") (pintype "passive"))
      (node (ref "R2-PINH1") (pin "1") (pinfunction "1_1") (pintype "passive"))
      (node (ref "SENSOR2") (pin "4") (pinfunction "SCK_4") (pintype "input"))
      (node (ref "U2") (pin "20") (pinfunction "IO22_20") (pintype "bidirectional"))
      (node (ref "U3") (pin "16") (pinfunction "SCL_16") (pintype "input"))
      (node (ref "U4") (pin "7") (pinfunction "SCL_7") (pintype "input"))
    )
    (net (code "54") (name "SDA") (class "Default")
      (node (ref "J3") (pin "3") (pinfunction "3_3") (pintype "passive"))
      (node (ref "R1-PINH") (pin "1") (pinfunction "1_1") (pintype "passive"))
      (node (ref "SENSOR2") (pin "3") (pinfunction "SDI_3") (pintype "bidirectional"))
      (node (ref "U2") (pin "19") (pinfunction "IO21_19") (pintype "bidirectional"))
      (node (ref "U3") (pin "15") (pinfunction "SDA_15") (pintype "bidirectional"))
      (node (ref "U4") (pin "8") (pinfunction "SDA_8") (pintype "bidirectional"))
    )
    (net (code "55") (name "SRC") (class "Default")
      (node (ref "C4") (pin "2") (pinfunction "2_2") (pintype "passive"))
      (node (ref "D5") (pin "2") (pinfunction "K_2") (pintype "bidirectional"))
      (node (ref "L1") (pin "1") (pinfunction "1_1") (pintype "passive"))
      (node (ref "Q3") (pin "3") (pinfunction "D_3") (pintype "bidirectional"))
    )
    (net (code "56") (name "SS_SD") (class "Default")
      (node (ref "J4") (pin "P2") (pinfunction "CD/DAT3_P2") (pintype "bidirectional"))
      (node (ref "U2") (pin "4") (pinfunction "IO4_4") (pintype "bidirectional"))
    )
    (net (code "57") (name "TX") (class "Default")
      (node (ref "TP1") (pin "TP") (pinfunction "TP_TP") (pintype "input"))
      (node (ref "U2") (pin "25") (pinfunction "TXD0/GPIO16_25") (pintype "bidirectional"))
    )
    (net (code "58") (name "USB_D+") (class "Default")
      (node (ref "D1") (pin "4") (pinfunction "I/O2_1_4") (pintype "bidirectional"))
      (node (ref "U2") (pin "14") (pinfunction "IO13_14") (pintype "bidirectional"))
    )
    (net (code "59") (name "USB_D-") (class "Default")
      (node (ref "D1") (pin "2") (pinfunction "I/O1_1_2") (pintype "bidirectional"))
      (node (ref "U2") (pin "13") (pinfunction "IO12_13") (pintype "bidirectional"))
    )
    (net (code "60") (name "VBAT") (class "Default")
      (node (ref "C2_BAT") (pin "1") (pinfunction "1_1") (pintype "passive"))
      (node (ref "Q1") (pin "1") (pinfunction "D_1") (pintype "bidirectional"))
      (node (ref "TP3") (pin "TP") (pinfunction "TP_TP") (pintype "input"))
      (node (ref "U4") (pin "2") (pinfunction "CELL_2") (pintype "power_in"))
      (node (ref "U4") (pin "3") (pinfunction "VDD_3") (pintype "power_in"))
      (node (ref "U5") (pin "3") (pinfunction "VBAT_3") (pintype "power_in"))
    )
    (net (code "61") (name "VBUS") (class "Default")
      (node (ref "C1_BAT") (pin "1") (pinfunction "1_1") (pintype "passive"))
      (node (ref "C4_USB") (pin "1") (pinfunction "1_1") (pintype "passive"))
      (node (ref "C5_USB") (pin "1") (pinfunction "1_1") (pintype "passive"))
      (node (ref "CHG_LED") (pin "A") (pinfunction "A_A") (pintype "passive"))
      (node (ref "D1") (pin "6") (pinfunction "VBUS_6") (pintype "bidirectional"))
      (node (ref "D2") (pin "1") (pinfunction "ANODE_1") (pintype "bidirectional"))
      (node (ref "PFMF.050.1") (pin "2") (pinfunction "2_2") (pintype "passive"))
      (node (ref "Q1") (pin "2") (pinfunction "G_2") (pintype "bidirectional"))
      (node (ref "R1_PWRUSB") (pin "2") (pinfunction "2_2") (pintype "passive"))
      (node (ref "TP14") (pin "TP") (pinfunction "TP_TP") (pintype "input"))
      (node (ref "U5") (pin "4") (pinfunction "VIN_4") (pintype "power_in"))
    )
    (net (code "62") (name "VRTC") (class "Default")
      (node (ref "C10_SUPERCAP") (pin "1") (pinfunction "1_1") (pintype "passive"))
      (node (ref "C8") (pin "1") (pinfunction "1_1") (pintype "passive"))
      (node (ref "R_CAPACITOR") (pin "1") (pinfunction "1_1") (pintype "passive"))
      (node (ref "U3") (pin "14") (pinfunction "VBAT_14") (pintype "power_in"))
    )
    (net (code "63") (name "VUSB") (class "Default")
      (node (ref "J2") (pin "A4") (pinfunction "A4_A4") (pintype "bidirectional"))
      (node (ref "J2") (pin "A9") (pinfunction "A9_A9") (pintype "bidirectional"))
      (node (ref "J2") (pin "B4") (pinfunction "B4_B4") (pintype "bidirectional"))
      (node (ref "J2") (pin "B9") (pinfunction "B9_B9") (pintype "bidirectional"))
      (node (ref "PFMF.050.1") (pin "1") (pinfunction "1_1") (pintype "passive"))
    )
    (net (code "64") (name "unconnected-(IC1-NC-Pad4)") (class "Default")
      (node (ref "IC1") (pin "4") (pinfunction "NC_4") (pintype "no_connect"))
    )
    (net (code "65") (name "unconnected-(IC4-NC-Pad4)") (class "Default")
      (node (ref "IC4") (pin "4") (pinfunction "NC_4") (pintype "no_connect"))
    )
    (net (code "66") (name "unconnected-(J1-Pad1)") (class "Default")
      (node (ref "J1") (pin "1") (pinfunction "1_1") (pintype "bidirectional"))
    )
    (net (code "67") (name "unconnected-(J1-Pad6)") (class "Default")
      (node (ref "J1") (pin "6") (pinfunction "6_6") (pintype "bidirectional"))
    )
    (net (code "68") (name "unconnected-(J1-Pad7)") (class "Default")
      (node (ref "J1") (pin "7") (pinfunction "7_7") (pintype "bidirectional"))
    )
    (net (code "69") (name "unconnected-(J2-PadA8)") (class "Default")
      (node (ref "J2") (pin "A8") (pinfunction "A8_A8") (pintype "bidirectional"))
    )
    (net (code "70") (name "unconnected-(J2-PadB8)") (class "Default")
      (node (ref "J2") (pin "B8") (pinfunction "B8_B8") (pintype "bidirectional"))
    )
    (net (code "71") (name "unconnected-(J4-DAT1-PadP8)") (class "Default")
      (node (ref "J4") (pin "P8") (pinfunction "DAT1_P8") (pintype "bidirectional"))
    )
    (net (code "72") (name "unconnected-(J4-DAT2-PadP1)") (class "Default")
      (node (ref "J4") (pin "P1") (pinfunction "DAT2_P1") (pintype "bidirectional"))
    )
    (net (code "73") (name "unconnected-(J4-DETECTION_1-PadS1)") (class "Default")
      (node (ref "J4") (pin "S1") (pinfunction "DETECTION_1_S1") (pintype "bidirectional"))
    )
    (net (code "74") (name "unconnected-(J4-DETECTION_2-PadS2)") (class "Default")
      (node (ref "J4") (pin "S2") (pinfunction "DETECTION_2_S2") (pintype "bidirectional"))
    )
    (net (code "75") (name "unconnected-(U2-NC-Pad22)") (class "Default")
      (node (ref "U2") (pin "22") (pinfunction "NC_22") (pintype "no_connect"))
    )
    (net (code "76") (name "unconnected-(U4-~{ALERT}-Pad5)") (class "Default")
      (node (ref "U4") (pin "5") (pinfunction "~{ALERT}_5") (pintype "output"))
    )
  )
)
